# STB_FanControl.net
KiCad netlist of a schematic drawn in Altium Designer
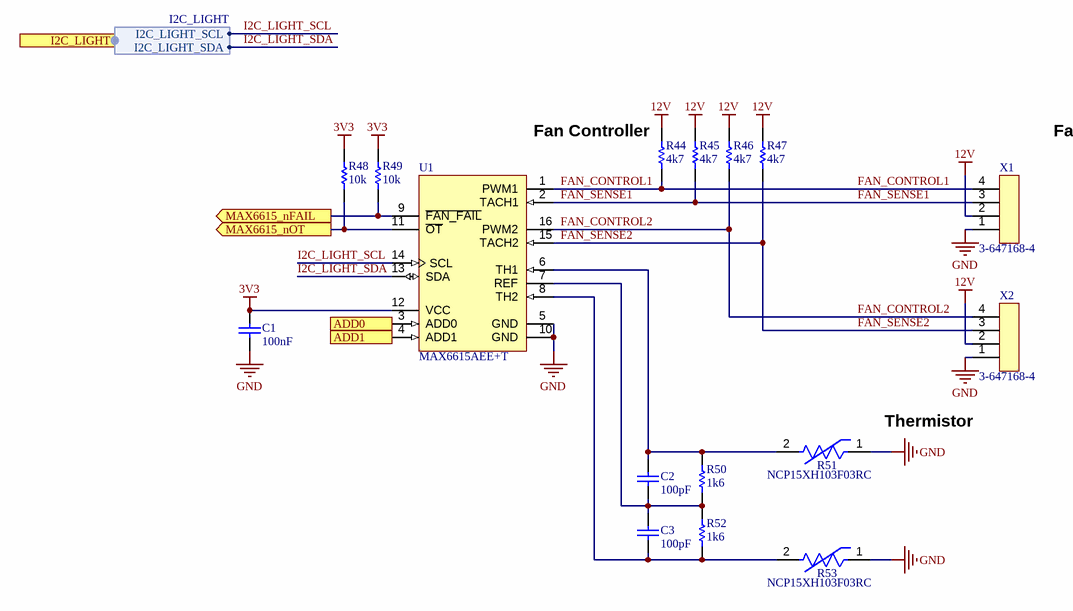
[diagram p0: STB_FanControl.SchDoc]

(export (version "E")
  (design (tool "Eeschema 10.0.6"))
  (components
    (comp (ref "C1")
      (value "100nF")
      (footprint "CAPC1050X55X23LL05T13")
      (description "Chip Capacitor, 100 nF, +/- 10%, 16 V, -55 to 125 degC, 0402 (1005 Metric), RoHS, Tape and Reel")
      (fields
        (field (name "MANUFACTURER") "Samsung Electro-Mechanics")
        (field (name "MANUFACTURER PART NUMBER") "CL05B104KO5NNNC")
      )
      (libsource (lib "Altium Content Vault") (part "CAP-NP-2"))
    )
    (comp (ref "C2")
      (value "100pF")
      (footprint "CAPC1005X56X25LL10T15")
      (fields
        (field (name "MANUFACTURER") "AVX Interconnect / Elco")
        (field (name "PART NUMBER") "04023A101KAT2A")
      )
      (libsource (lib "Altium Content Vault") (part "CAP"))
    )
    (comp (ref "C3")
      (value "100pF")
      (footprint "CAPC1005X56X25LL10T15")
      (fields
        (field (name "MANUFACTURER") "AVX Interconnect / Elco")
        (field (name "PART NUMBER") "04023A101KAT2A")
      )
      (libsource (lib "Altium Content Vault") (part "CAP"))
    )
    (comp (ref "R44")
      (value "4k7")
      (footprint "RESC1005X40X25LL05T10")
      (fields
        (field (name "MANUFACTURER") "Yageo / Phycomp")
        (field (name "PART NUMBER") "RC0402FR-074K7L")
        (field (name "TOLERANCE") "1%")
      )
      (libsource (lib "Altium Content Vault") (part "RES"))
    )
    (comp (ref "R45")
      (value "4k7")
      (footprint "RESC1005X40X25LL05T10")
      (fields
        (field (name "MANUFACTURER") "Yageo / Phycomp")
        (field (name "PART NUMBER") "RC0402FR-074K7L")
        (field (name "TOLERANCE") "1%")
      )
      (libsource (lib "Altium Content Vault") (part "RES"))
    )
    (comp (ref "R46")
      (value "4k7")
      (footprint "RESC1005X40X25LL05T10")
      (fields
        (field (name "MANUFACTURER") "Yageo / Phycomp")
        (field (name "PART NUMBER") "RC0402FR-074K7L")
        (field (name "TOLERANCE") "1%")
      )
      (libsource (lib "Altium Content Vault") (part "RES"))
    )
    (comp (ref "R47")
      (value "4k7")
      (footprint "RESC1005X40X25LL05T10")
      (fields
        (field (name "MANUFACTURER") "Yageo / Phycomp")
        (field (name "PART NUMBER") "RC0402FR-074K7L")
        (field (name "TOLERANCE") "1%")
      )
      (libsource (lib "Altium Content Vault") (part "RES"))
    )
    (comp (ref "R48")
      (value "10k")
      (footprint "RESC1005X40X25LL05T05")
      (description "Chip Resistor, 10 KOhm, +/- 1%, 0.1 W, -55 to 155 degC, 0402 (1005 Metric), RoHS, Tape and Reel")
      (fields (field (name "TOLERANCE") "1%") (field (name "MANUFACTURER") "Panasonic"))
      (libsource (lib "Altium Content Vault") (part "RES-2"))
    )
    (comp (ref "R49")
      (value "10k")
      (footprint "RESC1005X40X25LL05T05")
      (description "Chip Resistor, 10 KOhm, +/- 1%, 0.1 W, -55 to 155 degC, 0402 (1005 Metric), RoHS, Tape and Reel")
      (fields (field (name "TOLERANCE") "1%") (field (name "MANUFACTURER") "Panasonic"))
      (libsource (lib "Altium Content Vault") (part "RES-2"))
    )
    (comp (ref "R50")
      (value "1k6")
      (footprint "RESC1005X40X25LL05T10")
      (fields
        (field (name "MANUFACTURER") "Yageo / Phycomp")
        (field (name "PART NUMBER") "RC0402FR-071K6L")
        (field (name "TOLERANCE") "1%")
      )
      (libsource (lib "Altium Content Vault") (part "RES"))
    )
    (comp (ref "R51")
      (value "NCP15XH103F03RC")
      (footprint "FP-NCP15-NCU15-0_05-IPC_C")
      (description "NTC Thermistor for Temperature Sensor, 0402, 10kΩ, 1%, 0.1mA, 5V")
      (fields (field (name "TOLERANCE") "1%") (field (name "MANUFACTURER") "Murata"))
      (libsource (lib "Altium Content Vault") (part "3b148a6ebabc5fb4d708a66c052d352"))
    )
    (comp (ref "R52")
      (value "1k6")
      (footprint "RESC1005X40X25LL05T10")
      (fields
        (field (name "MANUFACTURER") "Yageo / Phycomp")
        (field (name "PART NUMBER") "RC0402FR-071K6L")
        (field (name "TOLERANCE") "1%")
      )
      (libsource (lib "Altium Content Vault") (part "RES"))
    )
    (comp (ref "R53")
      (value "NCP15XH103F03RC")
      (footprint "FP-NCP15-NCU15-0_05-IPC_C")
      (description "NTC Thermistor for Temperature Sensor, 0402, 10kΩ, 1%, 0.1mA, 5V")
      (fields (field (name "TOLERANCE") "1%") (field (name "MANUFACTURER") "Murata"))
      (libsource (lib "Altium Content Vault") (part "3b148a6ebabc5fb4d708a66c052d352"))
    )
    (comp (ref "U1")
      (value "MAX6615AEE+T")
      (footprint "MAXM-E16+1_M")
      (fields (field (name "GENERIC PART NUMBER") "MAX6615") (field (name "MANUFACTURER") "Maxim"))
      (libsource (lib "Altium Content Vault") (part "MAX6615-E16X1"))
    )
    (comp (ref "X1")
      (value "3-647168-4")
      (footprint "3-647168-4")
      (fields
        (field (name "MANUFACTURER") "TE Connectivity")
        (field (name "MANUFACTURER PART NUMBER") "3-647166-4")
      )
      (libsource (lib "STB_Schlib") (part "3-647168-4"))
    )
    (comp (ref "X2")
      (value "3-647168-4")
      (footprint "3-647168-4")
      (fields
        (field (name "MANUFACTURER") "TE Connectivity")
        (field (name "MANUFACTURER PART NUMBER") "3-647166-4")
      )
      (libsource (lib "STB_Schlib") (part "3-647168-4"))
    )
  )
  (nets
    (net (code "2") (name "/ADD0") (class "Default")
      (node (ref "U1") (pin "3") (pinfunction "ADD0_3") (pintype "input"))
    )
    (net (code "3") (name "/ADD1") (class "Default")
      (node (ref "U1") (pin "4") (pinfunction "ADD1_4") (pintype "input"))
    )
    (net (code "4") (name "/FAN_CONTROL1") (class "Default")
      (node (ref "R44") (pin "1") (pinfunction "1_1") (pintype "passive"))
      (node (ref "U1") (pin "1") (pinfunction "PWM1_1") (pintype "open_collector"))
      (node (ref "X1") (pin "4") (pintype "passive"))
    )
    (net (code "5") (name "/FAN_CONTROL2") (class "Default")
      (node (ref "R46") (pin "1") (pinfunction "1_1") (pintype "passive"))
      (node (ref "U1") (pin "16") (pinfunction "PWM2_16") (pintype "open_collector"))
      (node (ref "X2") (pin "4") (pintype "passive"))
    )
    (net (code "6") (name "/FAN_SENSE1") (class "Default")
      (node (ref "R45") (pin "1") (pinfunction "1_1") (pintype "passive"))
      (node (ref "U1") (pin "2") (pinfunction "TACH1_2") (pintype "input"))
      (node (ref "X1") (pin "3") (pintype "passive"))
    )
    (net (code "7") (name "/FAN_SENSE2") (class "Default")
      (node (ref "R47") (pin "1") (pinfunction "1_1") (pintype "passive"))
      (node (ref "U1") (pin "15") (pinfunction "TACH2_15") (pintype "input"))
      (node (ref "X2") (pin "3") (pintype "passive"))
    )
    (net (code "8") (name "/I2C_LIGHT_SCL") (class "Default")
      (node (ref "U1") (pin "14") (pinfunction "SCL_14") (pintype "input"))
    )
    (net (code "9") (name "/I2C_LIGHT_SDA") (class "Default")
      (node (ref "U1") (pin "13") (pinfunction "SDA_13") (pintype "bidirectional"))
    )
    (net (code "10") (name "/MAX6615_nFAIL") (class "Default")
      (node (ref "R49") (pin "1") (pinfunction "1_1") (pintype "passive"))
      (node (ref "U1") (pin "9") (pinfunction "~{FAN_FAIL}_9") (pintype "tri_state"))
    )
    (net (code "11") (name "/MAX6615_nOT") (class "Default")
      (node (ref "R48") (pin "1") (pinfunction "1_1") (pintype "passive"))
      (node (ref "U1") (pin "11") (pinfunction "~{OT}_11") (pintype "tri_state"))
    )
    (net (code "13") (name "3V3") (class "Default")
      (node (ref "C1") (pin "2") (pinfunction "2_2") (pintype "passive"))
      (node (ref "R48") (pin "2") (pinfunction "2_2") (pintype "passive"))
      (node (ref "R49") (pin "2") (pinfunction "2_2") (pintype "passive"))
      (node (ref "U1") (pin "12") (pinfunction "VCC_12") (pintype "power_in"))
    )
    (net (code "14") (name "12V") (class "Default")
      (node (ref "R44") (pin "2") (pinfunction "2_2") (pintype "passive"))
      (node (ref "R45") (pin "2") (pinfunction "2_2") (pintype "passive"))
      (node (ref "R46") (pin "2") (pinfunction "2_2") (pintype "passive"))
      (node (ref "R47") (pin "2") (pinfunction "2_2") (pintype "passive"))
      (node (ref "X1") (pin "2") (pintype "passive"))
      (node (ref "X2") (pin "2") (pintype "passive"))
    )
    (net (code "15") (name "GND") (class "Default")
      (node (ref "C1") (pin "1") (pinfunction "1_1") (pintype "passive"))
      (node (ref "R51") (pin "1") (pinfunction "1_1") (pintype "passive"))
      (node (ref "R53") (pin "1") (pinfunction "1_1") (pintype "passive"))
      (node (ref "U1") (pin "10") (pinfunction "GND_10") (pintype "power_in"))
      (node (ref "U1") (pin "5") (pinfunction "GND_5") (pintype "power_in"))
      (node (ref "X1") (pin "1") (pintype "passive"))
      (node (ref "X2") (pin "1") (pintype "passive"))
    )
    (net (code "16") (name "Net-(U1-REF)") (class "Default")
      (node (ref "C2") (pin "1") (pinfunction "1_1") (pintype "passive"))
      (node (ref "C3") (pin "2") (pinfunction "2_2") (pintype "passive"))
      (node (ref "R50") (pin "1") (pinfunction "1_1") (pintype "passive"))
      (node (ref "R52") (pin "2") (pinfunction "2_2") (pintype "passive"))
      (node (ref "U1") (pin "7") (pinfunction "REF_7") (pintype "tri_state"))
    )
    (net (code "17") (name "Net-(U1-TH1)") (class "Default")
      (node (ref "C2") (pin "2") (pinfunction "2_2") (pintype "passive"))
      (node (ref "R50") (pin "2") (pinfunction "2_2") (pintype "passive"))
      (node (ref "R51") (pin "2") (pinfunction "2_2") (pintype "passive"))
      (node (ref "U1") (pin "6") (pinfunction "TH1_6") (pintype "input"))
    )
    (net (code "18") (name "Net-(U1-TH2)") (class "Default")
      (node (ref "C3") (pin "1") (pinfunction "1_1") (pintype "passive"))
      (node (ref "R52") (pin "1") (pinfunction "1_1") (pintype "passive"))
      (node (ref "R53") (pin "2") (pinfunction "2_2") (pintype "passive"))
      (node (ref "U1") (pin "8") (pinfunction "TH2_8") (pintype "input"))
    )
  )
)
